# 8relay_breakout.net
KiCad netlist of a schematic drawn in Altium Designer
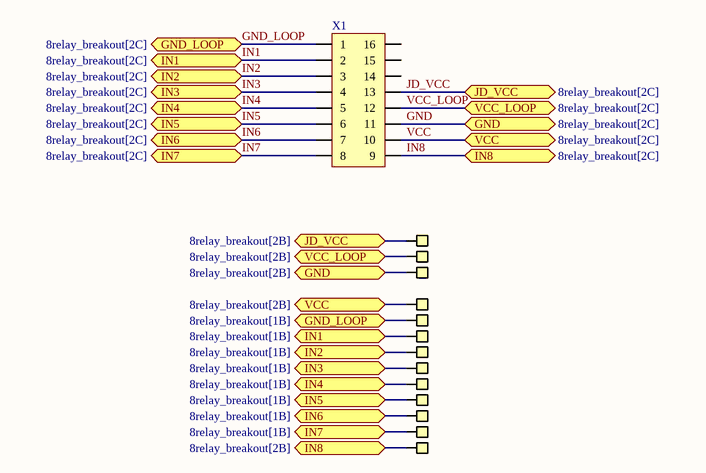
[diagram p0: 8relay_breakout.SchDoc]

(export (version "E")
  (design (tool "Eeschema 10.0.6"))
  (components
    (comp (ref "X1")
      (value "TERM BLOCK 16POS 45DEG 5MM PCB")
      (footprint "PHEONIX-1988943")
      (description "16 Position Wire to Board Terminal Block 45° (135°) Angle with Board 0.197\" (5.00mm) Through Hole")
      (libsource (lib "Connectors") (part "PHEONIX-1988943"))
    )
    (comp (ref "X2")
      (value "GenericPinHeader(0.1in)")
      (footprint "GenericPinHeader(.1in)")
      (description "Generic .1in(2.54mm) pitch pin header")
      (libsource (lib "Connectors") (part "GenericPinHeader(0.1in)"))
    )
    (comp (ref "X3")
      (value "GenericPinHeader(0.1in)")
      (footprint "GenericPinHeader(.1in)")
      (description "Generic .1in(2.54mm) pitch pin header")
      (libsource (lib "Connectors") (part "GenericPinHeader(0.1in)"))
    )
    (comp (ref "X4")
      (value "GenericPinHeader(0.1in)")
      (footprint "GenericPinHeader(.1in)")
      (description "Generic .1in(2.54mm) pitch pin header")
      (libsource (lib "Connectors") (part "GenericPinHeader(0.1in)"))
    )
    (comp (ref "X5")
      (value "GenericPinHeader(0.1in)")
      (footprint "GenericPinHeader(.1in)")
      (description "Generic .1in(2.54mm) pitch pin header")
      (libsource (lib "Connectors") (part "GenericPinHeader(0.1in)"))
    )
    (comp (ref "X6")
      (value "GenericPinHeader(0.1in)")
      (footprint "GenericPinHeader(.1in)")
      (description "Generic .1in(2.54mm) pitch pin header")
      (libsource (lib "Connectors") (part "GenericPinHeader(0.1in)"))
    )
    (comp (ref "X7")
      (value "GenericPinHeader(0.1in)")
      (footprint "GenericPinHeader(.1in)")
      (description "Generic .1in(2.54mm) pitch pin header")
      (libsource (lib "Connectors") (part "GenericPinHeader(0.1in)"))
    )
    (comp (ref "X8")
      (value "GenericPinHeader(0.1in)")
      (footprint "GenericPinHeader(.1in)")
      (description "Generic .1in(2.54mm) pitch pin header")
      (libsource (lib "Connectors") (part "GenericPinHeader(0.1in)"))
    )
    (comp (ref "X9")
      (value "GenericPinHeader(0.1in)")
      (footprint "GenericPinHeader(.1in)")
      (description "Generic .1in(2.54mm) pitch pin header")
      (libsource (lib "Connectors") (part "GenericPinHeader(0.1in)"))
    )
    (comp (ref "X10")
      (value "GenericPinHeader(0.1in)")
      (footprint "GenericPinHeader(.1in)")
      (description "Generic .1in(2.54mm) pitch pin header")
      (libsource (lib "Connectors") (part "GenericPinHeader(0.1in)"))
    )
    (comp (ref "X11")
      (value "GenericPinHeader(0.1in)")
      (footprint "GenericPinHeader(.1in)")
      (description "Generic .1in(2.54mm) pitch pin header")
      (libsource (lib "Connectors") (part "GenericPinHeader(0.1in)"))
    )
    (comp (ref "X12")
      (value "GenericPinHeader(0.1in)")
      (footprint "GenericPinHeader(.1in)")
      (description "Generic .1in(2.54mm) pitch pin header")
      (libsource (lib "Connectors") (part "GenericPinHeader(0.1in)"))
    )
    (comp (ref "X13")
      (value "GenericPinHeader(0.1in)")
      (footprint "GenericPinHeader(.1in)")
      (description "Generic .1in(2.54mm) pitch pin header")
      (libsource (lib "Connectors") (part "GenericPinHeader(0.1in)"))
    )
    (comp (ref "X14")
      (value "GenericPinHeader(0.1in)")
      (footprint "GenericPinHeader(.1in)")
      (description "Generic .1in(2.54mm) pitch pin header")
      (libsource (lib "Connectors") (part "GenericPinHeader(0.1in)"))
    )
  )
  (nets
    (net (code "1") (name "/GND") (class "Default")
      (node (ref "X1") (pin "11") (pinfunction "11_11") (pintype "passive"))
      (node (ref "X2") (pin "1") (pinfunction "Pin_1") (pintype "passive"))
    )
    (net (code "2") (name "/GND_LOOP") (class "Default")
      (node (ref "X1") (pin "1") (pinfunction "1_1") (pintype "passive"))
      (node (ref "X4") (pin "1") (pinfunction "Pin_1") (pintype "passive"))
    )
    (net (code "3") (name "/IN1") (class "Default")
      (node (ref "X1") (pin "2") (pinfunction "2_2") (pintype "passive"))
      (node (ref "X5") (pin "1") (pinfunction "Pin_1") (pintype "passive"))
    )
    (net (code "4") (name "/IN2") (class "Default")
      (node (ref "X1") (pin "3") (pinfunction "3_3") (pintype "passive"))
      (node (ref "X6") (pin "1") (pinfunction "Pin_1") (pintype "passive"))
    )
    (net (code "5") (name "/IN3") (class "Default")
      (node (ref "X1") (pin "4") (pinfunction "4_4") (pintype "passive"))
      (node (ref "X7") (pin "1") (pinfunction "Pin_1") (pintype "passive"))
    )
    (net (code "6") (name "/IN4") (class "Default")
      (node (ref "X1") (pin "5") (pinfunction "5_5") (pintype "passive"))
      (node (ref "X8") (pin "1") (pinfunction "Pin_1") (pintype "passive"))
    )
    (net (code "7") (name "/IN5") (class "Default")
      (node (ref "X1") (pin "6") (pinfunction "6_6") (pintype "passive"))
      (node (ref "X9") (pin "1") (pinfunction "Pin_1") (pintype "passive"))
    )
    (net (code "8") (name "/IN6") (class "Default")
      (node (ref "X1") (pin "7") (pinfunction "7_7") (pintype "passive"))
      (node (ref "X10") (pin "1") (pinfunction "Pin_1") (pintype "passive"))
    )
    (net (code "9") (name "/IN7") (class "Default")
      (node (ref "X1") (pin "8") (pinfunction "8_8") (pintype "passive"))
      (node (ref "X11") (pin "1") (pinfunction "Pin_1") (pintype "passive"))
    )
    (net (code "10") (name "/IN8") (class "Default")
      (node (ref "X1") (pin "9") (pinfunction "9_9") (pintype "passive"))
      (node (ref "X12") (pin "1") (pinfunction "Pin_1") (pintype "passive"))
    )
    (net (code "11") (name "/JD_VCC") (class "Default")
      (node (ref "X1") (pin "13") (pinfunction "13_13") (pintype "passive"))
      (node (ref "X13") (pin "1") (pinfunction "Pin_1") (pintype "passive"))
    )
    (net (code "12") (name "/VCC") (class "Default")
      (node (ref "X1") (pin "10") (pinfunction "10_10") (pintype "passive"))
      (node (ref "X3") (pin "1") (pinfunction "Pin_1") (pintype "passive"))
    )
    (net (code "13") (name "/VCC_LOOP") (class "Default")
      (node (ref "X1") (pin "12") (pinfunction "12_12") (pintype "passive"))
      (node (ref "X14") (pin "1") (pinfunction "Pin_1") (pintype "passive"))
    )
    (net (code "14") (name "unconnected-(X1-Pad14)") (class "Default")
      (node (ref "X1") (pin "14") (pinfunction "14_14") (pintype "passive"))
    )
    (net (code "15") (name "unconnected-(X1-Pad15)") (class "Default")
      (node (ref "X1") (pin "15") (pinfunction "15_15") (pintype "passive"))
    )
    (net (code "16") (name "unconnected-(X1-Pad16)") (class "Default")
      (node (ref "X1") (pin "16") (pinfunction "16_16") (pintype "passive"))
    )
  )
)
